# ProProject__-TI__2024-06-05.net
KiCad netlist of a schematic drawn in EasyEDA Pro
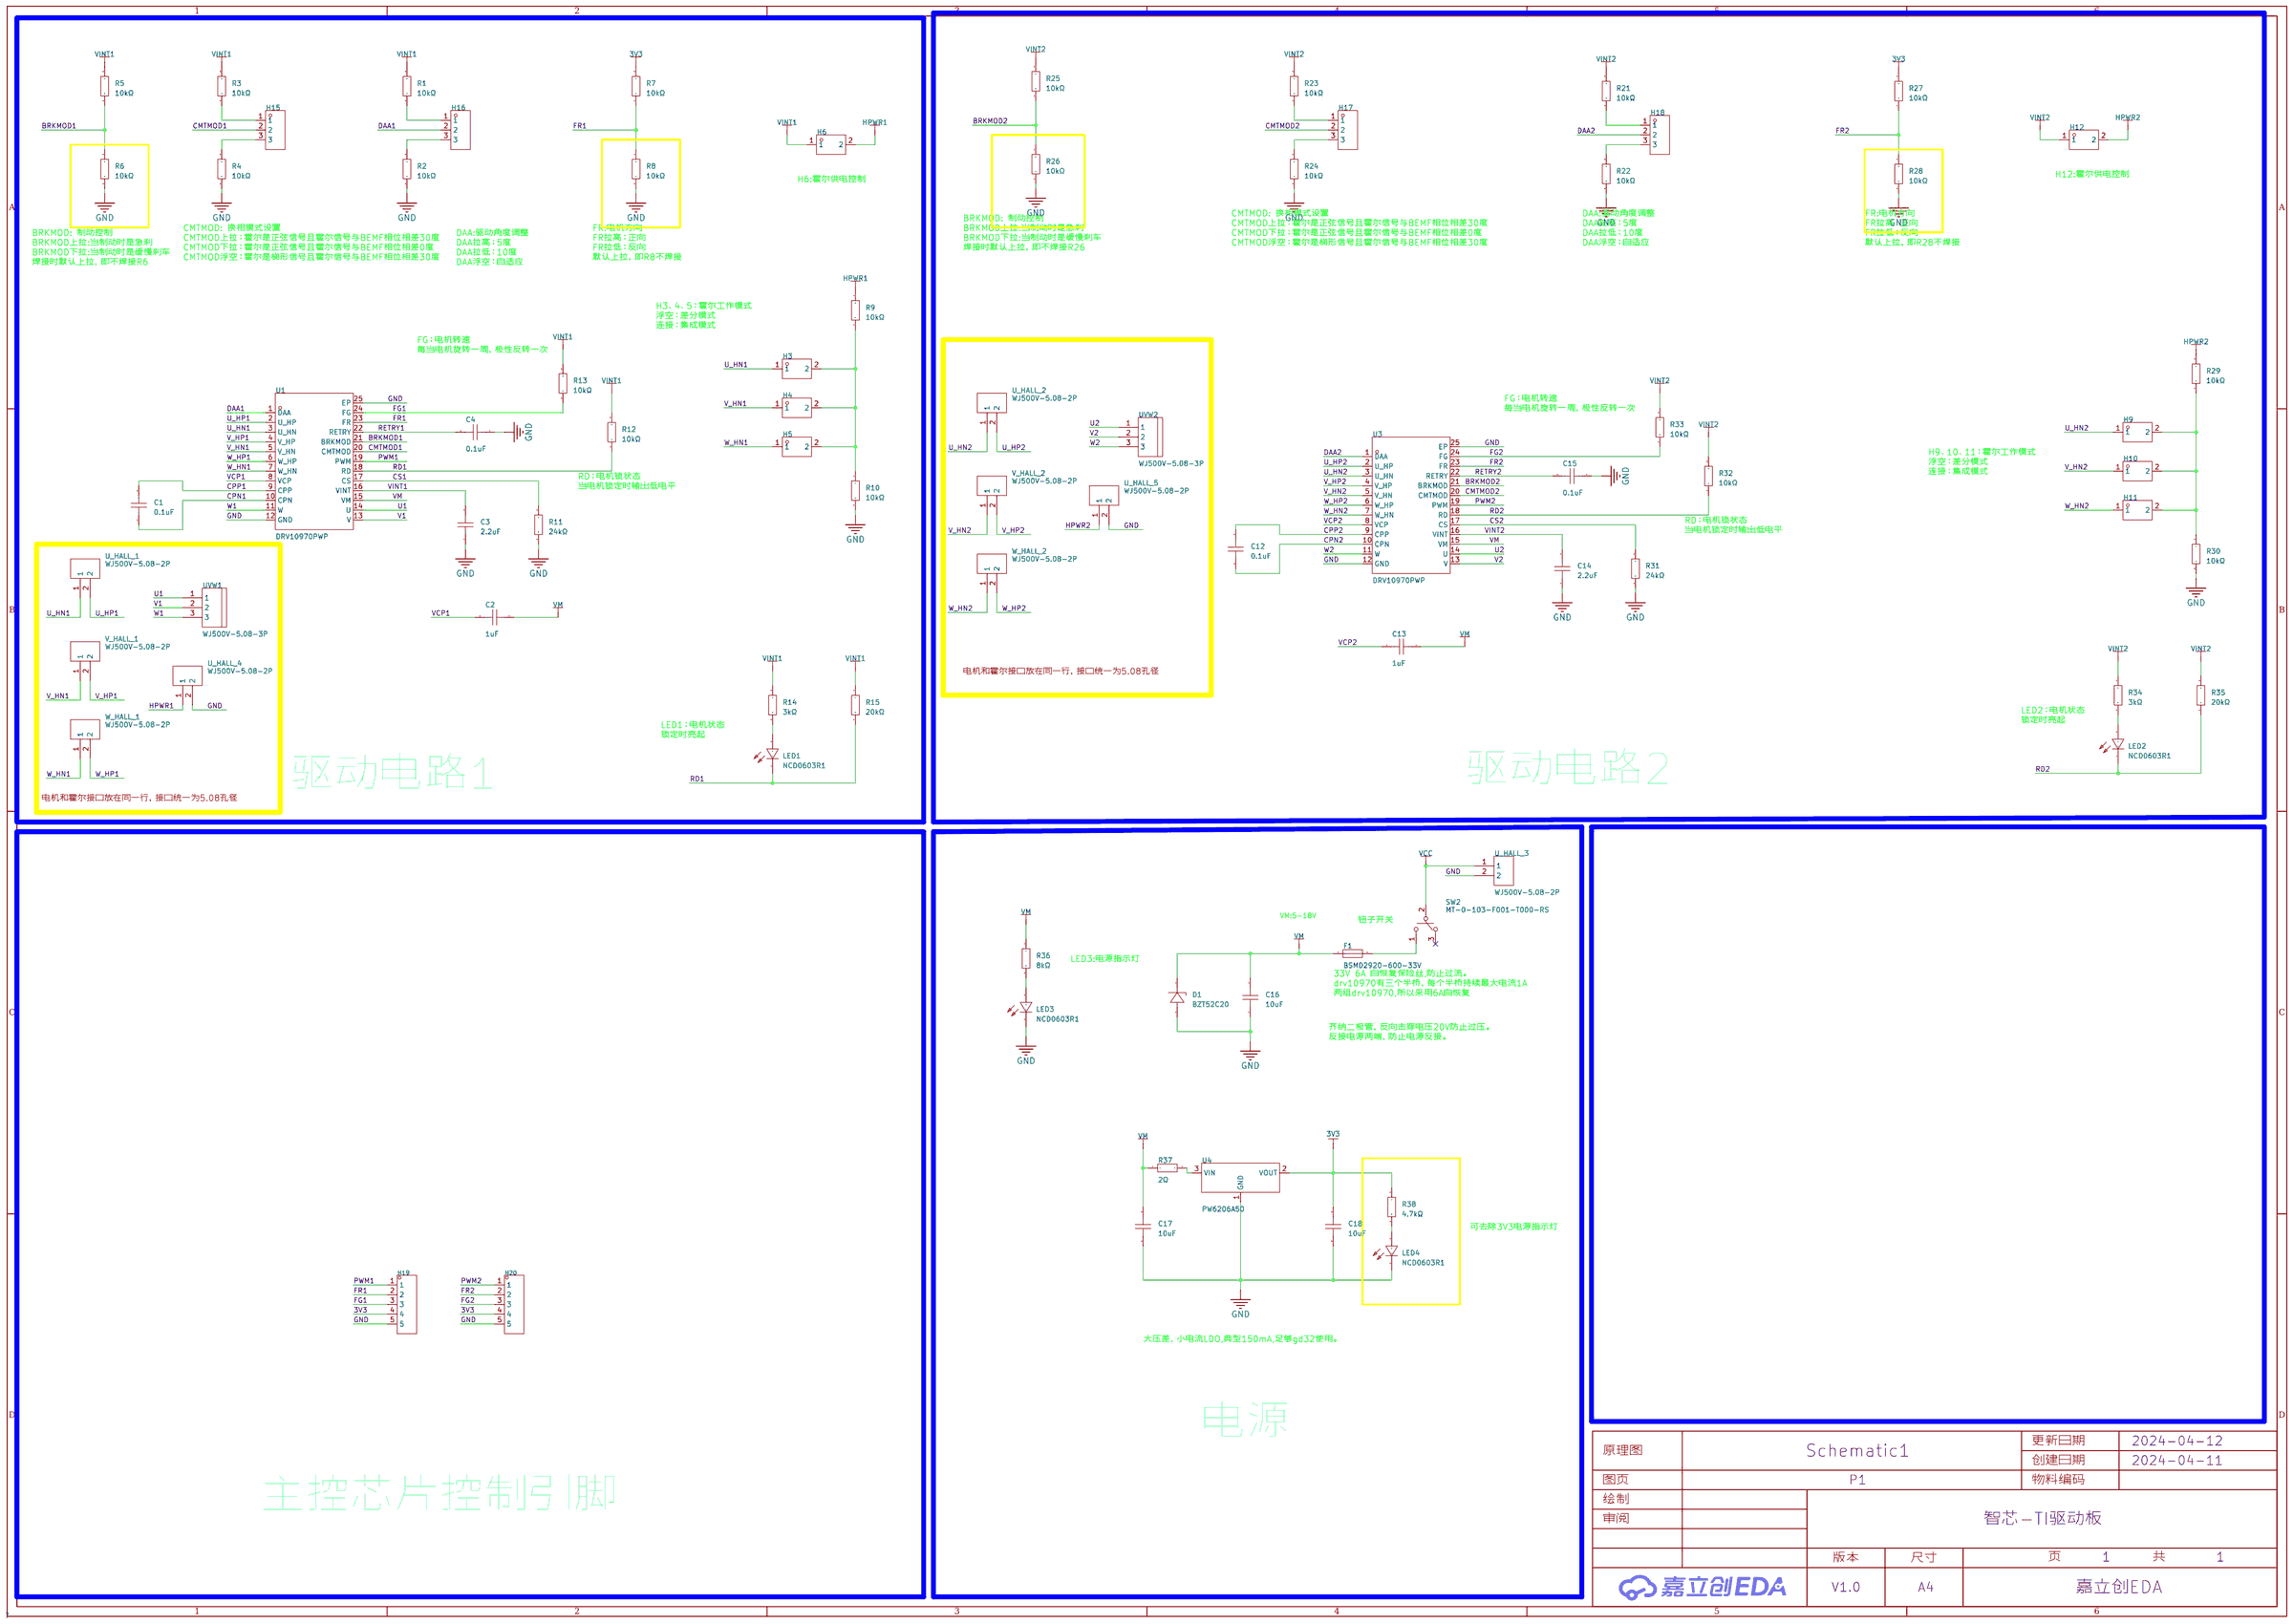
[diagram p0: schematic sheet]

(export (version "E")
  (design (tool "Eeschema 10.0.6"))
  (components
    (comp (ref "C1")
      (value "0.1uF")
      (footprint "easyedapro:C0603")
      (description "容值:100nF;精度:±10%;额定电压:50V;材质(温度系数):X7R;")
      (fields
        (field (name "Manufacturer Part") "CC0603KRX7R9BB104")
        (field (name "Manufacturer") "YAGEO(国巨)")
      )
      (libsource (lib "easyedapro") (part "CC0603KRX7R9BB104"))
    )
    (comp (ref "C2")
      (value "1uF")
      (footprint "easyedapro:C0603")
      (description "容值:100nF;精度:±10%;额定电压:50V;材质(温度系数):X7R;")
      (fields
        (field (name "Manufacturer Part") "CC0603KRX7R9BB104")
        (field (name "Manufacturer") "YAGEO(国巨)")
      )
      (libsource (lib "easyedapro") (part "CC0603KRX7R9BB104"))
    )
    (comp (ref "C3")
      (value "2.2uF")
      (footprint "easyedapro:C0603")
      (description "容值:100nF;精度:±10%;额定电压:50V;材质(温度系数):X7R;")
      (fields
        (field (name "Manufacturer Part") "CC0603KRX7R9BB104")
        (field (name "Manufacturer") "YAGEO(国巨)")
      )
      (libsource (lib "easyedapro") (part "CC0603KRX7R9BB104"))
    )
    (comp (ref "C4")
      (value "0.1uF")
      (footprint "easyedapro:C0603")
      (description "容值:100nF;精度:±10%;额定电压:50V;材质(温度系数):X7R;")
      (fields
        (field (name "Manufacturer Part") "CC0603KRX7R9BB104")
        (field (name "Manufacturer") "YAGEO(国巨)")
      )
      (libsource (lib "easyedapro") (part "CC0603KRX7R9BB104"))
    )
    (comp (ref "C12")
      (value "0.1uF")
      (footprint "easyedapro:C0603")
      (description "容值:100nF;精度:±10%;额定电压:50V;材质(温度系数):X7R;")
      (fields
        (field (name "Manufacturer Part") "CC0603KRX7R9BB104")
        (field (name "Manufacturer") "YAGEO(国巨)")
      )
      (libsource (lib "easyedapro") (part "CC0603KRX7R9BB104"))
    )
    (comp (ref "C13")
      (value "1uF")
      (footprint "easyedapro:C0603")
      (description "容值:100nF;精度:±10%;额定电压:50V;材质(温度系数):X7R;")
      (fields
        (field (name "Manufacturer Part") "CC0603KRX7R9BB104")
        (field (name "Manufacturer") "YAGEO(国巨)")
      )
      (libsource (lib "easyedapro") (part "CC0603KRX7R9BB104"))
    )
    (comp (ref "C14")
      (value "2.2uF")
      (footprint "easyedapro:C0603")
      (description "容值:100nF;精度:±10%;额定电压:50V;材质(温度系数):X7R;")
      (fields
        (field (name "Manufacturer Part") "CC0603KRX7R9BB104")
        (field (name "Manufacturer") "YAGEO(国巨)")
      )
      (libsource (lib "easyedapro") (part "CC0603KRX7R9BB104"))
    )
    (comp (ref "C15")
      (value "0.1uF")
      (footprint "easyedapro:C0603")
      (description "容值:100nF;精度:±10%;额定电压:50V;材质(温度系数):X7R;")
      (fields
        (field (name "Manufacturer Part") "CC0603KRX7R9BB104")
        (field (name "Manufacturer") "YAGEO(国巨)")
      )
      (libsource (lib "easyedapro") (part "CC0603KRX7R9BB104"))
    )
    (comp (ref "C16")
      (value "10uF")
      (footprint "easyedapro:C0603")
      (description "容值:100nF;精度:±10%;额定电压:50V;材质(温度系数):X7R;")
      (fields
        (field (name "Manufacturer Part") "CC0603KRX7R9BB104")
        (field (name "Manufacturer") "YAGEO(国巨)")
      )
      (libsource (lib "easyedapro") (part "CC0603KRX7R9BB104"))
    )
    (comp (ref "C17")
      (value "10uF")
      (footprint "easyedapro:C0603")
      (description "容值:100nF;精度:±10%;额定电压:50V;材质(温度系数):X7R;")
      (fields
        (field (name "Manufacturer Part") "CC0603KRX7R9BB104")
        (field (name "Manufacturer") "YAGEO(国巨)")
      )
      (libsource (lib "easyedapro") (part "CC0603KRX7R9BB104"))
    )
    (comp (ref "C18")
      (value "10uF")
      (footprint "easyedapro:C0603")
      (description "容值:100nF;精度:±10%;额定电压:50V;材质(温度系数):X7R;")
      (fields
        (field (name "Manufacturer Part") "CC0603KRX7R9BB104")
        (field (name "Manufacturer") "YAGEO(国巨)")
      )
      (libsource (lib "easyedapro") (part "CC0603KRX7R9BB104"))
    )
    (comp (ref "D1")
      (value "BZT52C20")
      (footprint "easyedapro:SOD-123_L2.7-W1.6-LS3.7-RD-1")
      (description "二极管配置:独立式;稳压值(标称值):20V;稳压值(范围):18.8V~21.2V;功率:500mW;精度:-;")
      (fields (field (name "Manufacturer") "BORN(伯恩半导体)"))
      (libsource (lib "easyedapro") (part "BZT52C20_C511888"))
    )
    (comp (ref "F1")
      (value "BSMD2920-600-33V")
      (footprint "easyedapro:F2920")
      (description "最大电压:16V;最大电流:40A;保持电流:6A;跳闸电流:12A;")
      (fields (field (name "Manufacturer") "BHFUSE(佰宏)"))
      (libsource (lib "easyedapro") (part "BSMD2920-600-16V"))
    )
    (comp (ref "H3")
      (value "~")
      (footprint "easyedapro:HDR-TH_2P-P2.54-V-M-2")
      (libsource (lib "easyedapro") (part "HDR-M-2.54_2x1"))
    )
    (comp (ref "H4")
      (value "~")
      (footprint "easyedapro:HDR-TH_2P-P2.54-V-M-2")
      (libsource (lib "easyedapro") (part "HDR-M-2.54_2x1"))
    )
    (comp (ref "H5")
      (value "~")
      (footprint "easyedapro:HDR-TH_2P-P2.54-V-M-2")
      (libsource (lib "easyedapro") (part "HDR-M-2.54_2x1"))
    )
    (comp (ref "H6")
      (value "~")
      (footprint "easyedapro:HDR-TH_2P-P2.54-V-M-2")
      (libsource (lib "easyedapro") (part "HDR-M-2.54_2x1"))
    )
    (comp (ref "H9")
      (value "~")
      (footprint "easyedapro:HDR-TH_2P-P2.54-V-M-2")
      (libsource (lib "easyedapro") (part "HDR-M-2.54_2x1"))
    )
    (comp (ref "H10")
      (value "~")
      (footprint "easyedapro:HDR-TH_2P-P2.54-V-M-2")
      (libsource (lib "easyedapro") (part "HDR-M-2.54_2x1"))
    )
    (comp (ref "H11")
      (value "~")
      (footprint "easyedapro:HDR-TH_2P-P2.54-V-M-2")
      (libsource (lib "easyedapro") (part "HDR-M-2.54_2x1"))
    )
    (comp (ref "H12")
      (value "~")
      (footprint "easyedapro:HDR-TH_2P-P2.54-V-M-2")
      (libsource (lib "easyedapro") (part "HDR-M-2.54_2x1"))
    )
    (comp (ref "H15")
      (value "~")
      (footprint "easyedapro:HDR-TH_3P-P2.54-V-M")
      (libsource (lib "easyedapro") (part "PZ254V-11-03P_C2937625"))
    )
    (comp (ref "H16")
      (value "~")
      (footprint "easyedapro:HDR-TH_3P-P2.54-V-M")
      (libsource (lib "easyedapro") (part "PZ254V-11-03P_C2937625"))
    )
    (comp (ref "H17")
      (value "~")
      (footprint "easyedapro:HDR-TH_3P-P2.54-V-M")
      (libsource (lib "easyedapro") (part "PZ254V-11-03P_C2937625"))
    )
    (comp (ref "H18")
      (value "~")
      (footprint "easyedapro:HDR-TH_3P-P2.54-V-M")
      (libsource (lib "easyedapro") (part "PZ254V-11-03P_C2937625"))
    )
    (comp (ref "H19")
      (value "~")
      (footprint "easyedapro:HDR-TH_5P-P2.54-V-M")
      (libsource (lib "easyedapro") (part "MTP125-1105S1"))
    )
    (comp (ref "H20")
      (value "~")
      (footprint "easyedapro:HDR-TH_5P-P2.54-V-M")
      (libsource (lib "easyedapro") (part "MTP125-1105S1"))
    )
    (comp (ref "LED1")
      (value "NCD0603R1")
      (footprint "easyedapro:LED0603-RD_RED")
      (fields (field (name "Manufacturer") "国星光电"))
      (libsource (lib "easyedapro") (part "FC-DA1608HRK-620D"))
    )
    (comp (ref "LED2")
      (value "NCD0603R1")
      (footprint "easyedapro:LED0603-RD_RED")
      (fields (field (name "Manufacturer") "国星光电"))
      (libsource (lib "easyedapro") (part "FC-DA1608HRK-620D"))
    )
    (comp (ref "LED3")
      (value "NCD0603R1")
      (footprint "easyedapro:LED0603-RD_RED")
      (fields (field (name "Manufacturer") "国星光电"))
      (libsource (lib "easyedapro") (part "FC-DA1608HRK-620D"))
    )
    (comp (ref "LED4")
      (value "NCD0603R1")
      (footprint "easyedapro:LED0603-RD_RED")
      (fields (field (name "Manufacturer") "国星光电"))
      (libsource (lib "easyedapro") (part "FC-DA1608HRK-620D"))
    )
    (comp (ref "R1")
      (value "10kΩ")
      (footprint "easyedapro:R0603")
      (description "电阻类型:厚膜电阻;阻值:10kΩ;精度:±1%;功率:100mW;最大工作电压:75V;温度系数:±100ppm/°C;")
      (fields
        (field (name "Manufacturer Part") "0603WAF1002T5E")
        (field (name "Manufacturer") "UNI-ROYAL(厚声)")
      )
      (libsource (lib "easyedapro") (part "0603WAF1002T5E"))
    )
    (comp (ref "R2")
      (value "10kΩ")
      (footprint "easyedapro:R0603")
      (description "电阻类型:厚膜电阻;阻值:10kΩ;精度:±1%;功率:100mW;最大工作电压:75V;温度系数:±100ppm/°C;")
      (fields
        (field (name "Manufacturer Part") "0603WAF1002T5E")
        (field (name "Manufacturer") "UNI-ROYAL(厚声)")
      )
      (libsource (lib "easyedapro") (part "0603WAF1002T5E"))
    )
    (comp (ref "R3")
      (value "10kΩ")
      (footprint "easyedapro:R0603")
      (description "电阻类型:厚膜电阻;阻值:10kΩ;精度:±1%;功率:100mW;最大工作电压:75V;温度系数:±100ppm/°C;")
      (fields
        (field (name "Manufacturer Part") "0603WAF1002T5E")
        (field (name "Manufacturer") "UNI-ROYAL(厚声)")
      )
      (libsource (lib "easyedapro") (part "0603WAF1002T5E"))
    )
    (comp (ref "R4")
      (value "10kΩ")
      (footprint "easyedapro:R0603")
      (description "电阻类型:厚膜电阻;阻值:10kΩ;精度:±1%;功率:100mW;最大工作电压:75V;温度系数:±100ppm/°C;")
      (fields
        (field (name "Manufacturer Part") "0603WAF1002T5E")
        (field (name "Manufacturer") "UNI-ROYAL(厚声)")
      )
      (libsource (lib "easyedapro") (part "0603WAF1002T5E"))
    )
    (comp (ref "R5")
      (value "10kΩ")
      (footprint "easyedapro:R0603")
      (description "电阻类型:厚膜电阻;阻值:10kΩ;精度:±1%;功率:100mW;最大工作电压:75V;温度系数:±100ppm/°C;")
      (fields
        (field (name "Manufacturer Part") "0603WAF1002T5E")
        (field (name "Manufacturer") "UNI-ROYAL(厚声)")
      )
      (libsource (lib "easyedapro") (part "0603WAF1002T5E"))
    )
    (comp (ref "R6")
      (value "10kΩ")
      (footprint "easyedapro:R0603")
      (description "电阻类型:厚膜电阻;阻值:10kΩ;精度:±1%;功率:100mW;最大工作电压:75V;温度系数:±100ppm/°C;")
      (fields
        (field (name "Manufacturer Part") "0603WAF1002T5E")
        (field (name "Manufacturer") "UNI-ROYAL(厚声)")
      )
      (libsource (lib "easyedapro") (part "0603WAF1002T5E"))
    )
    (comp (ref "R7")
      (value "10kΩ")
      (footprint "easyedapro:R0603")
      (description "电阻类型:厚膜电阻;阻值:10kΩ;精度:±1%;功率:100mW;最大工作电压:75V;温度系数:±100ppm/°C;")
      (fields
        (field (name "Manufacturer Part") "0603WAF1002T5E")
        (field (name "Manufacturer") "UNI-ROYAL(厚声)")
      )
      (libsource (lib "easyedapro") (part "0603WAF1002T5E"))
    )
    (comp (ref "R8")
      (value "10kΩ")
      (footprint "easyedapro:R0603")
      (description "电阻类型:厚膜电阻;阻值:10kΩ;精度:±1%;功率:100mW;最大工作电压:75V;温度系数:±100ppm/°C;")
      (fields
        (field (name "Manufacturer Part") "0603WAF1002T5E")
        (field (name "Manufacturer") "UNI-ROYAL(厚声)")
      )
      (libsource (lib "easyedapro") (part "0603WAF1002T5E"))
    )
    (comp (ref "R9")
      (value "10kΩ")
      (footprint "easyedapro:R0603")
      (description "电阻类型:厚膜电阻;阻值:10kΩ;精度:±1%;功率:100mW;最大工作电压:75V;温度系数:±100ppm/°C;")
      (fields
        (field (name "Manufacturer Part") "0603WAF1002T5E")
        (field (name "Manufacturer") "UNI-ROYAL(厚声)")
      )
      (libsource (lib "easyedapro") (part "0603WAF1002T5E"))
    )
    (comp (ref "R10")
      (value "10kΩ")
      (footprint "easyedapro:R0603")
      (description "电阻类型:厚膜电阻;阻值:10kΩ;精度:±1%;功率:100mW;最大工作电压:75V;温度系数:±100ppm/°C;")
      (fields
        (field (name "Manufacturer Part") "0603WAF1002T5E")
        (field (name "Manufacturer") "UNI-ROYAL(厚声)")
      )
      (libsource (lib "easyedapro") (part "0603WAF1002T5E"))
    )
    (comp (ref "R11")
      (value "24kΩ")
      (footprint "easyedapro:R0603")
      (description "电阻类型:厚膜电阻;阻值:10kΩ;精度:±1%;功率:100mW;最大工作电压:75V;温度系数:±100ppm/°C;")
      (fields
        (field (name "Manufacturer Part") "0603WAF1002T5E")
        (field (name "Manufacturer") "UNI-ROYAL(厚声)")
      )
      (libsource (lib "easyedapro") (part "0603WAF1002T5E"))
    )
    (comp (ref "R12")
      (value "10kΩ")
      (footprint "easyedapro:R0603")
      (description "电阻类型:厚膜电阻;阻值:10kΩ;精度:±1%;功率:100mW;最大工作电压:75V;温度系数:±100ppm/°C;")
      (fields
        (field (name "Manufacturer Part") "0603WAF1002T5E")
        (field (name "Manufacturer") "UNI-ROYAL(厚声)")
      )
      (libsource (lib "easyedapro") (part "0603WAF1002T5E"))
    )
    (comp (ref "R13")
      (value "10kΩ")
      (footprint "easyedapro:R0603")
      (description "电阻类型:厚膜电阻;阻值:10kΩ;精度:±1%;功率:100mW;最大工作电压:75V;温度系数:±100ppm/°C;")
      (fields
        (field (name "Manufacturer Part") "0603WAF1002T5E")
        (field (name "Manufacturer") "UNI-ROYAL(厚声)")
      )
      (libsource (lib "easyedapro") (part "0603WAF1002T5E"))
    )
    (comp (ref "R14")
      (value "3kΩ")
      (footprint "easyedapro:R0603")
      (description "电阻类型:厚膜电阻;阻值:10kΩ;精度:±1%;功率:100mW;最大工作电压:75V;温度系数:±100ppm/°C;")
      (fields
        (field (name "Manufacturer Part") "0603WAF1002T5E")
        (field (name "Manufacturer") "UNI-ROYAL(厚声)")
      )
      (libsource (lib "easyedapro") (part "0603WAF1002T5E"))
    )
    (comp (ref "R15")
      (value "20kΩ")
      (footprint "easyedapro:R0603")
      (description "电阻类型:厚膜电阻;阻值:10kΩ;精度:±1%;功率:100mW;最大工作电压:75V;温度系数:±100ppm/°C;")
      (fields
        (field (name "Manufacturer Part") "0603WAF1002T5E")
        (field (name "Manufacturer") "UNI-ROYAL(厚声)")
      )
      (libsource (lib "easyedapro") (part "0603WAF1002T5E"))
    )
    (comp (ref "R21")
      (value "10kΩ")
      (footprint "easyedapro:R0603")
      (description "电阻类型:厚膜电阻;阻值:10kΩ;精度:±1%;功率:100mW;最大工作电压:75V;温度系数:±100ppm/°C;")
      (fields
        (field (name "Manufacturer Part") "0603WAF1002T5E")
        (field (name "Manufacturer") "UNI-ROYAL(厚声)")
      )
      (libsource (lib "easyedapro") (part "0603WAF1002T5E"))
    )
    (comp (ref "R22")
      (value "10kΩ")
      (footprint "easyedapro:R0603")
      (description "电阻类型:厚膜电阻;阻值:10kΩ;精度:±1%;功率:100mW;最大工作电压:75V;温度系数:±100ppm/°C;")
      (fields
        (field (name "Manufacturer Part") "0603WAF1002T5E")
        (field (name "Manufacturer") "UNI-ROYAL(厚声)")
      )
      (libsource (lib "easyedapro") (part "0603WAF1002T5E"))
    )
    (comp (ref "R23")
      (value "10kΩ")
      (footprint "easyedapro:R0603")
      (description "电阻类型:厚膜电阻;阻值:10kΩ;精度:±1%;功率:100mW;最大工作电压:75V;温度系数:±100ppm/°C;")
      (fields
        (field (name "Manufacturer Part") "0603WAF1002T5E")
        (field (name "Manufacturer") "UNI-ROYAL(厚声)")
      )
      (libsource (lib "easyedapro") (part "0603WAF1002T5E"))
    )
    (comp (ref "R24")
      (value "10kΩ")
      (footprint "easyedapro:R0603")
      (description "电阻类型:厚膜电阻;阻值:10kΩ;精度:±1%;功率:100mW;最大工作电压:75V;温度系数:±100ppm/°C;")
      (fields
        (field (name "Manufacturer Part") "0603WAF1002T5E")
        (field (name "Manufacturer") "UNI-ROYAL(厚声)")
      )
      (libsource (lib "easyedapro") (part "0603WAF1002T5E"))
    )
    (comp (ref "R25")
      (value "10kΩ")
      (footprint "easyedapro:R0603")
      (description "电阻类型:厚膜电阻;阻值:10kΩ;精度:±1%;功率:100mW;最大工作电压:75V;温度系数:±100ppm/°C;")
      (fields
        (field (name "Manufacturer Part") "0603WAF1002T5E")
        (field (name "Manufacturer") "UNI-ROYAL(厚声)")
      )
      (libsource (lib "easyedapro") (part "0603WAF1002T5E"))
    )
    (comp (ref "R26")
      (value "10kΩ")
      (footprint "easyedapro:R0603")
      (description "电阻类型:厚膜电阻;阻值:10kΩ;精度:±1%;功率:100mW;最大工作电压:75V;温度系数:±100ppm/°C;")
      (fields
        (field (name "Manufacturer Part") "0603WAF1002T5E")
        (field (name "Manufacturer") "UNI-ROYAL(厚声)")
      )
      (libsource (lib "easyedapro") (part "0603WAF1002T5E"))
    )
    (comp (ref "R27")
      (value "10kΩ")
      (footprint "easyedapro:R0603")
      (description "电阻类型:厚膜电阻;阻值:10kΩ;精度:±1%;功率:100mW;最大工作电压:75V;温度系数:±100ppm/°C;")
      (fields
        (field (name "Manufacturer Part") "0603WAF1002T5E")
        (field (name "Manufacturer") "UNI-ROYAL(厚声)")
      )
      (libsource (lib "easyedapro") (part "0603WAF1002T5E"))
    )
    (comp (ref "R28")
      (value "10kΩ")
      (footprint "easyedapro:R0603")
      (description "电阻类型:厚膜电阻;阻值:10kΩ;精度:±1%;功率:100mW;最大工作电压:75V;温度系数:±100ppm/°C;")
      (fields
        (field (name "Manufacturer Part") "0603WAF1002T5E")
        (field (name "Manufacturer") "UNI-ROYAL(厚声)")
      )
      (libsource (lib "easyedapro") (part "0603WAF1002T5E"))
    )
    (comp (ref "R29")
      (value "10kΩ")
      (footprint "easyedapro:R0603")
      (description "电阻类型:厚膜电阻;阻值:10kΩ;精度:±1%;功率:100mW;最大工作电压:75V;温度系数:±100ppm/°C;")
      (fields
        (field (name "Manufacturer Part") "0603WAF1002T5E")
        (field (name "Manufacturer") "UNI-ROYAL(厚声)")
      )
      (libsource (lib "easyedapro") (part "0603WAF1002T5E"))
    )
    (comp (ref "R30")
      (value "10kΩ")
      (footprint "easyedapro:R0603")
      (description "电阻类型:厚膜电阻;阻值:10kΩ;精度:±1%;功率:100mW;最大工作电压:75V;温度系数:±100ppm/°C;")
      (fields
        (field (name "Manufacturer Part") "0603WAF1002T5E")
        (field (name "Manufacturer") "UNI-ROYAL(厚声)")
      )
      (libsource (lib "easyedapro") (part "0603WAF1002T5E"))
    )
    (comp (ref "R31")
      (value "24kΩ")
      (footprint "easyedapro:R0603")
      (description "电阻类型:厚膜电阻;阻值:10kΩ;精度:±1%;功率:100mW;最大工作电压:75V;温度系数:±100ppm/°C;")
      (fields
        (field (name "Manufacturer Part") "0603WAF1002T5E")
        (field (name "Manufacturer") "UNI-ROYAL(厚声)")
      )
      (libsource (lib "easyedapro") (part "0603WAF1002T5E"))
    )
    (comp (ref "R32")
      (value "10kΩ")
      (footprint "easyedapro:R0603")
      (description "电阻类型:厚膜电阻;阻值:10kΩ;精度:±1%;功率:100mW;最大工作电压:75V;温度系数:±100ppm/°C;")
      (fields
        (field (name "Manufacturer Part") "0603WAF1002T5E")
        (field (name "Manufacturer") "UNI-ROYAL(厚声)")
      )
      (libsource (lib "easyedapro") (part "0603WAF1002T5E"))
    )
    (comp (ref "R33")
      (value "10kΩ")
      (footprint "easyedapro:R0603")
      (description "电阻类型:厚膜电阻;阻值:10kΩ;精度:±1%;功率:100mW;最大工作电压:75V;温度系数:±100ppm/°C;")
      (fields
        (field (name "Manufacturer Part") "0603WAF1002T5E")
        (field (name "Manufacturer") "UNI-ROYAL(厚声)")
      )
      (libsource (lib "easyedapro") (part "0603WAF1002T5E"))
    )
    (comp (ref "R34")
      (value "3kΩ")
      (footprint "easyedapro:R0603")
      (description "电阻类型:厚膜电阻;阻值:10kΩ;精度:±1%;功率:100mW;最大工作电压:75V;温度系数:±100ppm/°C;")
      (fields
        (field (name "Manufacturer Part") "0603WAF1002T5E")
        (field (name "Manufacturer") "UNI-ROYAL(厚声)")
      )
      (libsource (lib "easyedapro") (part "0603WAF1002T5E"))
    )
    (comp (ref "R35")
      (value "20kΩ")
      (footprint "easyedapro:R0603")
      (description "电阻类型:厚膜电阻;阻值:10kΩ;精度:±1%;功率:100mW;最大工作电压:75V;温度系数:±100ppm/°C;")
      (fields
        (field (name "Manufacturer Part") "0603WAF1002T5E")
        (field (name "Manufacturer") "UNI-ROYAL(厚声)")
      )
      (libsource (lib "easyedapro") (part "0603WAF1002T5E"))
    )
    (comp (ref "R36")
      (value "8kΩ")
      (footprint "easyedapro:R0603")
      (description "电阻类型:厚膜电阻;阻值:10kΩ;精度:±1%;功率:100mW;最大工作电压:75V;温度系数:±100ppm/°C;")
      (fields
        (field (name "Manufacturer Part") "0603WAF1002T5E")
        (field (name "Manufacturer") "UNI-ROYAL(厚声)")
      )
      (libsource (lib "easyedapro") (part "0603WAF1002T5E"))
    )
    (comp (ref "R37")
      (value "2Ω")
      (footprint "easyedapro:R0603")
      (description "电阻类型:厚膜电阻;阻值:10kΩ;精度:±1%;功率:100mW;最大工作电压:75V;温度系数:±100ppm/°C;")
      (fields
        (field (name "Manufacturer Part") "0603WAF1002T5E")
        (field (name "Manufacturer") "UNI-ROYAL(厚声)")
      )
      (libsource (lib "easyedapro") (part "0603WAF1002T5E"))
    )
    (comp (ref "R38")
      (value "4.7kΩ")
      (footprint "easyedapro:R0603")
      (description "电阻类型:厚膜电阻;阻值:10kΩ;精度:±1%;功率:100mW;最大工作电压:75V;温度系数:±100ppm/°C;")
      (fields
        (field (name "Manufacturer Part") "0603WAF1002T5E")
        (field (name "Manufacturer") "UNI-ROYAL(厚声)")
      )
      (libsource (lib "easyedapro") (part "0603WAF1002T5E"))
    )
    (comp (ref "SW2")
      (value "MT-0-103-F001-T000-RS")
      (footprint "easyedapro:SW-TH_MT-0-103-A101-M200-RS")
      (description "电路结构:单刀双掷;机械寿命:-;额定电流:5A;额定电压(AC):125V;安装方式:直插;")
      (fields (field (name "Manufacturer") "YUEN FUNG(源丰)"))
      (libsource (lib "easyedapro") (part "MT-0-103-F001-T000-RS+PJ"))
    )
    (comp (ref "U1")
      (value "DRV10970PWP")
      (footprint "easyedapro:HTSSOP-24_L7.8-W4.4-P0.65-LS6.4-BL-EP")
      (description "驱动电机类型:无刷直流BLDC;电源电压:5V~18V;输出电流:1.5A;接口:PWM;")
      (fields (field (name "Manufacturer") "TI(德州仪器)"))
      (libsource (lib "easyedapro") (part "DRV10970PWP"))
    )
    (comp (ref "U3")
      (value "DRV10970PWP")
      (footprint "easyedapro:HTSSOP-24_L7.8-W4.4-P0.65-LS6.4-BL-EP")
      (description "驱动电机类型:无刷直流BLDC;电源电压:5V~18V;输出电流:1.5A;接口:PWM;")
      (fields (field (name "Manufacturer") "TI(德州仪器)"))
      (libsource (lib "easyedapro") (part "DRV10970PWP"))
    )
    (comp (ref "U4")
      (value "PW6206A50")
      (footprint "easyedapro:SOT-23-3_L2.9-W1.6-P1.90-LS2.8-BR")
      (description "IN: 4.5V-40V OUT:5V 250mA")
      (libsource (lib "easyedapro") (part "PW6206A50"))
    )
    (comp (ref "UVW1")
      (value "WJ500V-5.08-3P")
      (footprint "easyedapro:CONN-TH_3P-P5.00_WJ500V-5.08-3P")
      (fields (field (name "Manufacturer") "KANGNEX(康奈克斯电气)"))
      (libsource (lib "easyedapro") (part "WJ500V-5.08-3P-14-00A"))
    )
    (comp (ref "UVW2")
      (value "WJ500V-5.08-3P")
      (footprint "easyedapro:CONN-TH_3P-P5.00_WJ500V-5.08-3P")
      (fields (field (name "Manufacturer") "KANGNEX(康奈克斯电气)"))
      (libsource (lib "easyedapro") (part "WJ500V-5.08-3P-14-00A"))
    )
    (comp (ref "U_HALL_1")
      (value "WJ500V-5.08-2P")
      (footprint "easyedapro:CONN-TH_2P-P5.00_WJ500V-5.08-2P")
      (fields (field (name "Manufacturer") "KANGNEX(康奈克斯电气)"))
      (libsource (lib "easyedapro") (part "WJ500V-5.08-2P-14-00A"))
    )
    (comp (ref "U_HALL_2")
      (value "WJ500V-5.08-2P")
      (footprint "easyedapro:CONN-TH_2P-P5.00_WJ500V-5.08-2P")
      (fields (field (name "Manufacturer") "KANGNEX(康奈克斯电气)"))
      (libsource (lib "easyedapro") (part "WJ500V-5.08-2P-14-00A"))
    )
    (comp (ref "U_HALL_3")
      (value "WJ500V-5.08-2P")
      (footprint "easyedapro:CONN-TH_2P-P5.00_WJ500V-5.08-2P")
      (fields (field (name "Manufacturer") "KANGNEX(康奈克斯电气)"))
      (libsource (lib "easyedapro") (part "WJ500V-5.08-2P-14-00A"))
    )
    (comp (ref "U_HALL_4")
      (value "WJ500V-5.08-2P")
      (footprint "easyedapro:CONN-TH_2P-P5.00_WJ500V-5.08-2P")
      (fields (field (name "Manufacturer") "KANGNEX(康奈克斯电气)"))
      (libsource (lib "easyedapro") (part "WJ500V-5.08-2P-14-00A"))
    )
    (comp (ref "U_HALL_5")
      (value "WJ500V-5.08-2P")
      (footprint "easyedapro:CONN-TH_2P-P5.00_WJ500V-5.08-2P")
      (fields (field (name "Manufacturer") "KANGNEX(康奈克斯电气)"))
      (libsource (lib "easyedapro") (part "WJ500V-5.08-2P-14-00A"))
    )
    (comp (ref "V_HALL_1")
      (value "WJ500V-5.08-2P")
      (footprint "easyedapro:CONN-TH_2P-P5.00_WJ500V-5.08-2P")
      (fields (field (name "Manufacturer") "KANGNEX(康奈克斯电气)"))
      (libsource (lib "easyedapro") (part "WJ500V-5.08-2P-14-00A"))
    )
    (comp (ref "V_HALL_2")
      (value "WJ500V-5.08-2P")
      (footprint "easyedapro:CONN-TH_2P-P5.00_WJ500V-5.08-2P")
      (fields (field (name "Manufacturer") "KANGNEX(康奈克斯电气)"))
      (libsource (lib "easyedapro") (part "WJ500V-5.08-2P-14-00A"))
    )
    (comp (ref "W_HALL_1")
      (value "WJ500V-5.08-2P")
      (footprint "easyedapro:CONN-TH_2P-P5.00_WJ500V-5.08-2P")
      (fields (field (name "Manufacturer") "KANGNEX(康奈克斯电气)"))
      (libsource (lib "easyedapro") (part "WJ500V-5.08-2P-14-00A"))
    )
    (comp (ref "W_HALL_2")
      (value "WJ500V-5.08-2P")
      (footprint "easyedapro:CONN-TH_2P-P5.00_WJ500V-5.08-2P")
      (fields (field (name "Manufacturer") "KANGNEX(康奈克斯电气)"))
      (libsource (lib "easyedapro") (part "WJ500V-5.08-2P-14-00A"))
    )
  )
  (nets
    (net (code "1") (name "/BRKMOD1") (class "Default")
      (node (ref "R5") (pin "1") (pinfunction "1_1") (pintype "input"))
      (node (ref "R6") (pin "1") (pinfunction "1_1") (pintype "input"))
      (node (ref "U1") (pin "21") (pinfunction "BRKMOD_21") (pintype "unspecified"))
    )
    (net (code "2") (name "/BRKMOD2") (class "Default")
      (node (ref "R25") (pin "1") (pinfunction "1_1") (pintype "input"))
      (node (ref "R26") (pin "1") (pinfunction "1_1") (pintype "input"))
      (node (ref "U3") (pin "21") (pinfunction "BRKMOD_21") (pintype "unspecified"))
    )
    (net (code "3") (name "/CMTMOD1") (class "Default")
      (node (ref "H15") (pin "2") (pinfunction "2_2") (pintype "input"))
      (node (ref "U1") (pin "20") (pinfunction "CMTMOD_20") (pintype "unspecified"))
    )
    (net (code "4") (name "/CMTMOD2") (class "Default")
      (node (ref "H17") (pin "2") (pinfunction "2_2") (pintype "input"))
      (node (ref "U3") (pin "20") (pinfunction "CMTMOD_20") (pintype "unspecified"))
    )
    (net (code "5") (name "/CPN1") (class "Default")
      (node (ref "C1") (pin "1") (pinfunction "1_1") (pintype "unspecified"))
      (node (ref "U1") (pin "10") (pinfunction "CPN_10") (pintype "unspecified"))
    )
    (net (code "6") (name "/CPN2") (class "Default")
      (node (ref "C12") (pin "1") (pinfunction "1_1") (pintype "unspecified"))
      (node (ref "U3") (pin "10") (pinfunction "CPN_10") (pintype "unspecified"))
    )
    (net (code "7") (name "/CPP1") (class "Default")
      (node (ref "C1") (pin "2") (pinfunction "2_2") (pintype "unspecified"))
      (node (ref "U1") (pin "9") (pinfunction "CPP_9") (pintype "unspecified"))
    )
    (net (code "8") (name "/CPP2") (class "Default")
      (node (ref "C12") (pin "2") (pinfunction "2_2") (pintype "unspecified"))
      (node (ref "U3") (pin "9") (pinfunction "CPP_9") (pintype "unspecified"))
    )
    (net (code "9") (name "/CS1") (class "Default")
      (node (ref "R11") (pin "1") (pinfunction "1_1") (pintype "input"))
      (node (ref "U1") (pin "17") (pinfunction "CS_17") (pintype "unspecified"))
    )
    (net (code "10") (name "/CS2") (class "Default")
      (node (ref "R31") (pin "1") (pinfunction "1_1") (pintype "input"))
      (node (ref "U3") (pin "17") (pinfunction "CS_17") (pintype "unspecified"))
    )
    (net (code "11") (name "/DAA1") (class "Default")
      (node (ref "H16") (pin "2") (pinfunction "2_2") (pintype "input"))
      (node (ref "U1") (pin "1") (pinfunction "DAA_1") (pintype "unspecified"))
    )
    (net (code "12") (name "/DAA2") (class "Default")
      (node (ref "H18") (pin "2") (pinfunction "2_2") (pintype "input"))
      (node (ref "U3") (pin "1") (pinfunction "DAA_1") (pintype "unspecified"))
    )
    (net (code "13") (name "/FG1") (class "Default")
      (node (ref "H19") (pin "3") (pinfunction "3_3") (pintype "input"))
      (node (ref "R13") (pin "1") (pinfunction "1_1") (pintype "input"))
      (node (ref "U1") (pin "24") (pinfunction "FG_24") (pintype "unspecified"))
    )
    (net (code "14") (name "/FG2") (class "Default")
      (node (ref "H20") (pin "3") (pinfunction "3_3") (pintype "input"))
      (node (ref "R33") (pin "1") (pinfunction "1_1") (pintype "input"))
      (node (ref "U3") (pin "24") (pinfunction "FG_24") (pintype "unspecified"))
    )
    (net (code "15") (name "/FR1") (class "Default")
      (node (ref "H19") (pin "2") (pinfunction "2_2") (pintype "input"))
      (node (ref "R7") (pin "1") (pinfunction "1_1") (pintype "input"))
      (node (ref "R8") (pin "1") (pinfunction "1_1") (pintype "input"))
      (node (ref "U1") (pin "23") (pinfunction "FR_23") (pintype "unspecified"))
    )
    (net (code "16") (name "/FR2") (class "Default")
      (node (ref "H20") (pin "2") (pinfunction "2_2") (pintype "input"))
      (node (ref "R27") (pin "1") (pinfunction "1_1") (pintype "input"))
      (node (ref "R28") (pin "1") (pinfunction "1_1") (pintype "input"))
      (node (ref "U3") (pin "23") (pinfunction "FR_23") (pintype "unspecified"))
    )
    (net (code "17") (name "/PWM1") (class "Default")
      (node (ref "H19") (pin "1") (pinfunction "1_1") (pintype "input"))
      (node (ref "U1") (pin "19") (pinfunction "PWM_19") (pintype "unspecified"))
    )
    (net (code "18") (name "/PWM2") (class "Default")
      (node (ref "H20") (pin "1") (pinfunction "1_1") (pintype "input"))
      (node (ref "U3") (pin "19") (pinfunction "PWM_19") (pintype "unspecified"))
    )
    (net (code "19") (name "/RD1") (class "Default")
      (node (ref "LED1") (pin "1") (pinfunction "K_1") (pintype "input"))
      (node (ref "R12") (pin "1") (pinfunction "1_1") (pintype "input"))
      (node (ref "R15") (pin "2") (pinfunction "2_2") (pintype "input"))
      (node (ref "U1") (pin "18") (pinfunction "RD_18") (pintype "unspecified"))
    )
    (net (code "20") (name "/RD2") (class "Default")
      (node (ref "LED2") (pin "1") (pinfunction "K_1") (pintype "input"))
      (node (ref "R32") (pin "1") (pinfunction "1_1") (pintype "input"))
      (node (ref "R35") (pin "2") (pinfunction "2_2") (pintype "input"))
      (node (ref "U3") (pin "18") (pinfunction "RD_18") (pintype "unspecified"))
    )
    (net (code "21") (name "/RETRY1") (class "Default")
      (node (ref "C4") (pin "2") (pinfunction "2_2") (pintype "unspecified"))
      (node (ref "U1") (pin "22") (pinfunction "RETRY_22") (pintype "unspecified"))
    )
    (net (code "22") (name "/RETRY2") (class "Default")
      (node (ref "C15") (pin "2") (pinfunction "2_2") (pintype "unspecified"))
      (node (ref "U3") (pin "22") (pinfunction "RETRY_22") (pintype "unspecified"))
    )
    (net (code "23") (name "/U1") (class "Default")
      (node (ref "U1") (pin "14") (pinfunction "U_14") (pintype "unspecified"))
      (node (ref "UVW1") (pin "1") (pinfunction "1_1") (pintype "unspecified"))
    )
    (net (code "24") (name "/U2") (class "Default")
      (node (ref "U3") (pin "14") (pinfunction "U_14") (pintype "unspecified"))
      (node (ref "UVW2") (pin "1") (pinfunction "1_1") (pintype "unspecified"))
    )
    (net (code "25") (name "/U_HN1") (class "Default")
      (node (ref "H3") (pin "1") (pinfunction "1_1") (pintype "input"))
      (node (ref "U1") (pin "3") (pinfunction "U_HN_3") (pintype "unspecified"))
      (node (ref "U_HALL_1") (pin "1") (pinfunction "1_1") (pintype "unspecified"))
    )
    (net (code "26") (name "/U_HN2") (class "Default")
      (node (ref "H9") (pin "1") (pinfunction "1_1") (pintype "input"))
      (node (ref "U3") (pin "3") (pinfunction "U_HN_3") (pintype "unspecified"))
      (node (ref "U_HALL_2") (pin "1") (pinfunction "1_1") (pintype "unspecified"))
    )
    (net (code "27") (name "/U_HP1") (class "Default")
      (node (ref "U1") (pin "2") (pinfunction "U_HP_2") (pintype "unspecified"))
      (node (ref "U_HALL_1") (pin "2") (pinfunction "2_2") (pintype "unspecified"))
    )
    (net (code "28") (name "/U_HP2") (class "Default")
      (node (ref "U3") (pin "2") (pinfunction "U_HP_2") (pintype "unspecified"))
      (node (ref "U_HALL_2") (pin "2") (pinfunction "2_2") (pintype "unspecified"))
    )
    (net (code "29") (name "/V1") (class "Default")
      (node (ref "U1") (pin "13") (pinfunction "V_13") (pintype "unspecified"))
      (node (ref "UVW1") (pin "2") (pinfunction "2_2") (pintype "unspecified"))
    )
    (net (code "30") (name "/V2") (class "Default")
      (node (ref "U3") (pin "13") (pinfunction "V_13") (pintype "unspecified"))
      (node (ref "UVW2") (pin "2") (pinfunction "2_2") (pintype "unspecified"))
    )
    (net (code "31") (name "/VCP1") (class "Default")
      (node (ref "C2") (pin "2") (pinfunction "2_2") (pintype "unspecified"))
      (node (ref "U1") (pin "8") (pinfunction "VCP_8") (pintype "unspecified"))
    )
    (net (code "32") (name "/VCP2") (class "Default")
      (node (ref "C13") (pin "2") (pinfunction "2_2") (pintype "unspecified"))
      (node (ref "U3") (pin "8") (pinfunction "VCP_8") (pintype "unspecified"))
    )
    (net (code "33") (name "/V_HN1") (class "Default")
      (node (ref "H4") (pin "1") (pinfunction "1_1") (pintype "input"))
      (node (ref "U1") (pin "5") (pinfunction "V_HN_5") (pintype "unspecified"))
      (node (ref "V_HALL_1") (pin "1") (pinfunction "1_1") (pintype "unspecified"))
    )
    (net (code "34") (name "/V_HN2") (class "Default")
      (node (ref "H10") (pin "1") (pinfunction "1_1") (pintype "input"))
      (node (ref "U3") (pin "5") (pinfunction "V_HN_5") (pintype "unspecified"))
      (node (ref "V_HALL_2") (pin "1") (pinfunction "1_1") (pintype "unspecified"))
    )
    (net (code "35") (name "/V_HP1") (class "Default")
      (node (ref "U1") (pin "4") (pinfunction "V_HP_4") (pintype "unspecified"))
      (node (ref "V_HALL_1") (pin "2") (pinfunction "2_2") (pintype "unspecified"))
    )
    (net (code "36") (name "/V_HP2") (class "Default")
      (node (ref "U3") (pin "4") (pinfunction "V_HP_4") (pintype "unspecified"))
      (node (ref "V_HALL_2") (pin "2") (pinfunction "2_2") (pintype "unspecified"))
    )
    (net (code "37") (name "/W1") (class "Default")
      (node (ref "U1") (pin "11") (pinfunction "W_11") (pintype "unspecified"))
      (node (ref "UVW1") (pin "3") (pinfunction "3_3") (pintype "unspecified"))
    )
    (net (code "38") (name "/W2") (class "Default")
      (node (ref "U3") (pin "11") (pinfunction "W_11") (pintype "unspecified"))
      (node (ref "UVW2") (pin "3") (pinfunction "3_3") (pintype "unspecified"))
    )
    (net (code "39") (name "/W_HN1") (class "Default")
      (node (ref "H5") (pin "1") (pinfunction "1_1") (pintype "input"))
      (node (ref "U1") (pin "7") (pinfunction "W_HN_7") (pintype "unspecified"))
      (node (ref "W_HALL_1") (pin "1") (pinfunction "1_1") (pintype "unspecified"))
    )
    (net (code "40") (name "/W_HN2") (class "Default")
      (node (ref "H11") (pin "1") (pinfunction "1_1") (pintype "input"))
      (node (ref "U3") (pin "7") (pinfunction "W_HN_7") (pintype "unspecified"))
      (node (ref "W_HALL_2") (pin "1") (pinfunction "1_1") (pintype "unspecified"))
    )
    (net (code "41") (name "/W_HP1") (class "Default")
      (node (ref "U1") (pin "6") (pinfunction "W_HP_6") (pintype "unspecified"))
      (node (ref "W_HALL_1") (pin "2") (pinfunction "2_2") (pintype "unspecified"))
    )
    (net (code "42") (name "/W_HP2") (class "Default")
      (node (ref "U3") (pin "6") (pinfunction "W_HP_6") (pintype "unspecified"))
      (node (ref "W_HALL_2") (pin "2") (pinfunction "2_2") (pintype "unspecified"))
    )
    (net (code "43") (name "3V3") (class "Default")
      (node (ref "C18") (pin "1") (pinfunction "1_1") (pintype "unspecified"))
      (node (ref "H19") (pin "4") (pinfunction "4_4") (pintype "input"))
      (node (ref "H20") (pin "4") (pinfunction "4_4") (pintype "input"))
      (node (ref "R27") (pin "2") (pinfunction "2_2") (pintype "input"))
      (node (ref "R38") (pin "1") (pinfunction "1_1") (pintype "input"))
      (node (ref "R7") (pin "2") (pinfunction "2_2") (pintype "input"))
      (node (ref "U4") (pin "2") (pinfunction "VOUT_2") (pintype "input"))
    )
    (net (code "44") (name "GND") (class "Default")
      (node (ref "C14") (pin "1") (pinfunction "1_1") (pintype "unspecified"))
      (node (ref "C15") (pin "1") (pinfunction "1_1") (pintype "unspecified"))
      (node (ref "C16") (pin "2") (pinfunction "2_2") (pintype "unspecified"))
      (node (ref "C17") (pin "2") (pinfunction "2_2") (pintype "unspecified"))
      (node (ref "C18") (pin "2") (pinfunction "2_2") (pintype "unspecified"))
      (node (ref "C3") (pin "1") (pinfunction "1_1") (pintype "unspecified"))
      (node (ref "C4") (pin "1") (pinfunction "1_1") (pintype "unspecified"))
      (node (ref "D1") (pin "2") (pinfunction "A_2") (pintype "unspecified"))
      (node (ref "H19") (pin "5") (pinfunction "5_5") (pintype "input"))
      (node (ref "H20") (pin "5") (pinfunction "5_5") (pintype "input"))
      (node (ref "LED3") (pin "1") (pinfunction "K_1") (pintype "input"))
      (node (ref "LED4") (pin "1") (pinfunction "K_1") (pintype "input"))
      (node (ref "R10") (pin "2") (pinfunction "2_2") (pintype "input"))
      (node (ref "R11") (pin "2") (pinfunction "2_2") (pintype "input"))
      (node (ref "R2") (pin "2") (pinfunction "2_2") (pintype "input"))
      (node (ref "R22") (pin "2") (pinfunction "2_2") (pintype "input"))
      (node (ref "R24") (pin "2") (pinfunction "2_2") (pintype "input"))
      (node (ref "R26") (pin "2") (pinfunction "2_2") (pintype "input"))
      (node (ref "R28") (pin "2") (pinfunction "2_2") (pintype "input"))
      (node (ref "R30") (pin "2") (pinfunction "2_2") (pintype "input"))
      (node (ref "R31") (pin "2") (pinfunction "2_2") (pintype "input"))
      (node (ref "R4") (pin "2") (pinfunction "2_2") (pintype "input"))
      (node (ref "R6") (pin "2") (pinfunction "2_2") (pintype "input"))
      (node (ref "R8") (pin "2") (pinfunction "2_2") (pintype "input"))
      (node (ref "U1") (pin "12") (pinfunction "GND_12") (pintype "unspecified"))
      (node (ref "U1") (pin "25") (pinfunction "EP_25") (pintype "unspecified"))
      (node (ref "U3") (pin "12") (pinfunction "GND_12") (pintype "unspecified"))
      (node (ref "U3") (pin "25") (pinfunction "EP_25") (pintype "unspecified"))
      (node (ref "U4") (pin "1") (pinfunction "GND_1") (pintype "input"))
      (node (ref "U_HALL_3") (pin "2") (pinfunction "2_2") (pintype "unspecified"))
      (node (ref "U_HALL_4") (pin "2") (pinfunction "2_2") (pintype "unspecified"))
      (node (ref "U_HALL_5") (pin "2") (pinfunction "2_2") (pintype "unspecified"))
    )
    (net (code "45") (name "HPWR1") (class "Default")
      (node (ref "H6") (pin "2") (pinfunction "2_2") (pintype "input"))
      (node (ref "R9") (pin "2") (pinfunction "2_2") (pintype "input"))
      (node (ref "U_HALL_4") (pin "1") (pinfunction "1_1") (pintype "unspecified"))
    )
    (net (code "46") (name "HPWR2") (class "Default")
      (node (ref "H12") (pin "2") (pinfunction "2_2") (pintype "input"))
      (node (ref "R29") (pin "2") (pinfunction "2_2") (pintype "input"))
      (node (ref "U_HALL_5") (pin "1") (pinfunction "1_1") (pintype "unspecified"))
    )
    (net (code "47") (name "Net-(F1-Pad2)") (class "Default")
      (node (ref "F1") (pin "2") (pinfunction "2_2") (pintype "unspecified"))
      (node (ref "SW2") (pin "1") (pinfunction "1_1") (pintype "unspecified"))
    )
    (net (code "48") (name "Net-(H3-Pad2)") (class "Default")
      (node (ref "H3") (pin "2") (pinfunction "2_2") (pintype "input"))
      (node (ref "H4") (pin "2") (pinfunction "2_2") (pintype "input"))
      (node (ref "H5") (pin "2") (pinfunction "2_2") (pintype "input"))
      (node (ref "R10") (pin "1") (pinfunction "1_1") (pintype "input"))
      (node (ref "R9") (pin "1") (pinfunction "1_1") (pintype "input"))
    )
    (net (code "49") (name "Net-(H10-Pad2)") (class "Default")
      (node (ref "H10") (pin "2") (pinfunction "2_2") (pintype "input"))
      (node (ref "H11") (pin "2") (pinfunction "2_2") (pintype "input"))
      (node (ref "H9") (pin "2") (pinfunction "2_2") (pintype "input"))
      (node (ref "R29") (pin "1") (pinfunction "1_1") (pintype "input"))
      (node (ref "R30") (pin "1") (pinfunction "1_1") (pintype "input"))
    )
    (net (code "50") (name "Net-(H15-Pad1)") (class "Default")
      (node (ref "H15") (pin "1") (pinfunction "1_1") (pintype "input"))
      (node (ref "R3") (pin "1") (pinfunction "1_1") (pintype "input"))
    )
    (net (code "51") (name "Net-(H15-Pad3)") (class "Default")
      (node (ref "H15") (pin "3") (pinfunction "3_3") (pintype "input"))
      (node (ref "R4") (pin "1") (pinfunction "1_1") (pintype "input"))
    )
    (net (code "52") (name "Net-(H16-Pad1)") (class "Default")
      (node (ref "H16") (pin "1") (pinfunction "1_1") (pintype "input"))
      (node (ref "R1") (pin "1") (pinfunction "1_1") (pintype "input"))
    )
    (net (code "53") (name "Net-(H16-Pad3)") (class "Default")
      (node (ref "H16") (pin "3") (pinfunction "3_3") (pintype "input"))
      (node (ref "R2") (pin "1") (pinfunction "1_1") (pintype "input"))
    )
    (net (code "54") (name "Net-(H17-Pad1)") (class "Default")
      (node (ref "H17") (pin "1") (pinfunction "1_1") (pintype "input"))
      (node (ref "R23") (pin "1") (pinfunction "1_1") (pintype "input"))
    )
    (net (code "55") (name "Net-(H17-Pad3)") (class "Default")
      (node (ref "H17") (pin "3") (pinfunction "3_3") (pintype "input"))
      (node (ref "R24") (pin "1") (pinfunction "1_1") (pintype "input"))
    )
    (net (code "56") (name "Net-(H18-Pad1)") (class "Default")
      (node (ref "H18") (pin "1") (pinfunction "1_1") (pintype "input"))
      (node (ref "R21") (pin "1") (pinfunction "1_1") (pintype "input"))
    )
    (net (code "57") (name "Net-(H18-Pad3)") (class "Default")
      (node (ref "H18") (pin "3") (pinfunction "3_3") (pintype "input"))
      (node (ref "R22") (pin "1") (pinfunction "1_1") (pintype "input"))
    )
    (net (code "58") (name "Net-(LED1-A)") (class "Default")
      (node (ref "LED1") (pin "2") (pinfunction "A_2") (pintype "input"))
      (node (ref "R14") (pin "2") (pinfunction "2_2") (pintype "input"))
    )
    (net (code "59") (name "Net-(LED2-A)") (class "Default")
      (node (ref "LED2") (pin "2") (pinfunction "A_2") (pintype "input"))
      (node (ref "R34") (pin "2") (pinfunction "2_2") (pintype "input"))
    )
    (net (code "60") (name "Net-(LED3-A)") (class "Default")
      (node (ref "LED3") (pin "2") (pinfunction "A_2") (pintype "input"))
      (node (ref "R36") (pin "2") (pinfunction "2_2") (pintype "input"))
    )
    (net (code "61") (name "Net-(LED4-A)") (class "Default")
      (node (ref "LED4") (pin "2") (pinfunction "A_2") (pintype "input"))
      (node (ref "R38") (pin "2") (pinfunction "2_2") (pintype "input"))
    )
    (net (code "62") (name "Net-(U4-VIN)") (class "Default")
      (node (ref "R37") (pin "2") (pinfunction "2_2") (pintype "input"))
      (node (ref "U4") (pin "3") (pinfunction "VIN_3") (pintype "input"))
    )
    (net (code "63") (name "VCC") (class "Default")
      (node (ref "SW2") (pin "2") (pinfunction "2_2") (pintype "unspecified"))
      (node (ref "U_HALL_3") (pin "1") (pinfunction "1_1") (pintype "unspecified"))
    )
    (net (code "64") (name "VINT1") (class "Default")
      (node (ref "C3") (pin "2") (pinfunction "2_2") (pintype "unspecified"))
      (node (ref "H6") (pin "1") (pinfunction "1_1") (pintype "input"))
      (node (ref "R1") (pin "2") (pinfunction "2_2") (pintype "input"))
      (node (ref "R12") (pin "2") (pinfunction "2_2") (pintype "input"))
      (node (ref "R13") (pin "2") (pinfunction "2_2") (pintype "input"))
      (node (ref "R14") (pin "1") (pinfunction "1_1") (pintype "input"))
      (node (ref "R15") (pin "1") (pinfunction "1_1") (pintype "input"))
      (node (ref "R3") (pin "2") (pinfunction "2_2") (pintype "input"))
      (node (ref "R5") (pin "2") (pinfunction "2_2") (pintype "input"))
      (node (ref "U1") (pin "16") (pinfunction "VINT_16") (pintype "unspecified"))
    )
    (net (code "65") (name "VINT2") (class "Default")
      (node (ref "C14") (pin "2") (pinfunction "2_2") (pintype "unspecified"))
      (node (ref "H12") (pin "1") (pinfunction "1_1") (pintype "input"))
      (node (ref "R21") (pin "2") (pinfunction "2_2") (pintype "input"))
      (node (ref "R23") (pin "2") (pinfunction "2_2") (pintype "input"))
      (node (ref "R25") (pin "2") (pinfunction "2_2") (pintype "input"))
      (node (ref "R32") (pin "2") (pinfunction "2_2") (pintype "input"))
      (node (ref "R33") (pin "2") (pinfunction "2_2") (pintype "input"))
      (node (ref "R34") (pin "1") (pinfunction "1_1") (pintype "input"))
      (node (ref "R35") (pin "1") (pinfunction "1_1") (pintype "input"))
      (node (ref "U3") (pin "16") (pinfunction "VINT_16") (pintype "unspecified"))
    )
    (net (code "66") (name "VM") (class "Default")
      (node (ref "C13") (pin "1") (pinfunction "1_1") (pintype "unspecified"))
      (node (ref "C16") (pin "1") (pinfunction "1_1") (pintype "unspecified"))
      (node (ref "C17") (pin "1") (pinfunction "1_1") (pintype "unspecified"))
      (node (ref "C2") (pin "1") (pinfunction "1_1") (pintype "unspecified"))
      (node (ref "D1") (pin "1") (pinfunction "K_1") (pintype "unspecified"))
      (node (ref "F1") (pin "1") (pinfunction "1_1") (pintype "unspecified"))
      (node (ref "R36") (pin "1") (pinfunction "1_1") (pintype "input"))
      (node (ref "R37") (pin "1") (pinfunction "1_1") (pintype "input"))
      (node (ref "U1") (pin "15") (pinfunction "VM_15") (pintype "unspecified"))
      (node (ref "U3") (pin "15") (pinfunction "VM_15") (pintype "unspecified"))
    )
    (net (code "67") (name "unconnected-(SW2-Pad3)") (class "Default")
      (node (ref "SW2") (pin "3") (pinfunction "3_3") (pintype "unspecified+no_connect"))
    )
  )
)
